# riffle-CTL-0_2-throughhole.net
KiCad netlist of a schematic drawn in EAGLE
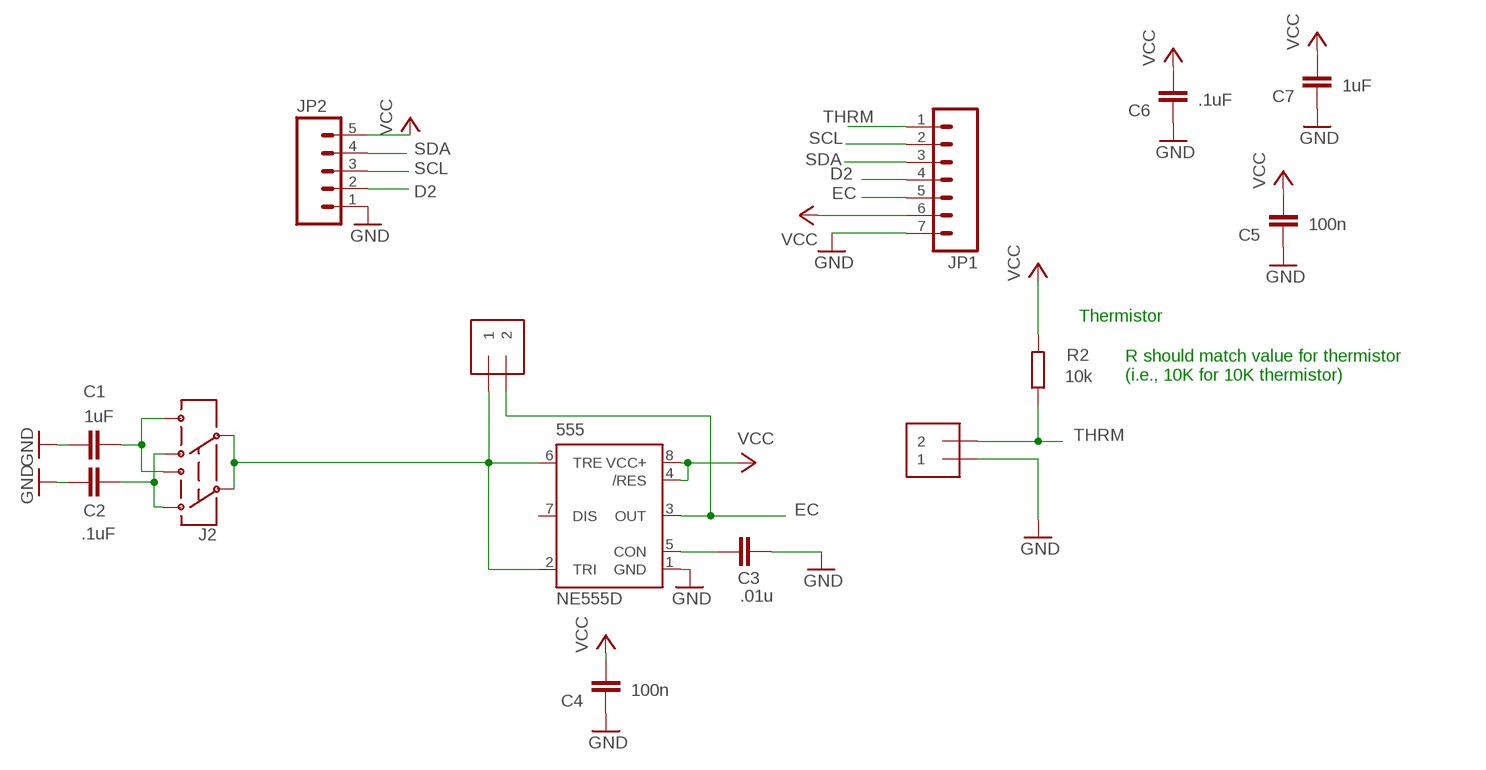
[diagram p0: schematic, sheet 1]

(export (version "E")
  (design (tool "Eeschema 10.0.6"))
  (components
    (comp (ref "555")
      (value "NE555D")
      (footprint "eagle-import:SO08@1")
      (libsource (lib "eagle-import") (part "NE555D"))
    )
    (comp (ref "C1")
      (value "1uF")
      (footprint "eagle-import:C0805")
      (libsource (lib "eagle-import") (part "C-EUC0805"))
    )
    (comp (ref "C2")
      (value ".1uF")
      (footprint "eagle-import:C0805")
      (libsource (lib "eagle-import") (part "C-EUC0805"))
    )
    (comp (ref "C3")
      (value ".01u")
      (footprint "eagle-import:C0805")
      (libsource (lib "eagle-import") (part "C-EUC0805"))
    )
    (comp (ref "C4")
      (value "100n")
      (footprint "eagle-import:C0805")
      (libsource (lib "eagle-import") (part "C-EUC0805"))
    )
    (comp (ref "C5")
      (value "100n")
      (footprint "eagle-import:C0805")
      (libsource (lib "eagle-import") (part "C-EUC0805"))
    )
    (comp (ref "C6")
      (value ".1uF")
      (footprint "eagle-import:C0805")
      (libsource (lib "eagle-import") (part "C-EUC0805"))
    )
    (comp (ref "C7")
      (value "1uF")
      (footprint "eagle-import:C0805")
      (libsource (lib "eagle-import") (part "C-EUC0805"))
    )
    (comp (ref "EC")
      (value "1X2-3.5MM")
      (footprint "eagle-import:1X2-3.5MM")
      (libsource (lib "eagle-import") (part "1X2-3.5MM"))
    )
    (comp (ref "J2")
      (value "AYZ0202")
      (footprint "eagle-import:AYZ0202")
      (libsource (lib "eagle-import") (part "AYZ0202"))
    )
    (comp (ref "JP1")
      (value "M07")
      (footprint "eagle-import:1X07")
      (libsource (lib "eagle-import") (part "M07"))
    )
    (comp (ref "JP2")
      (value "M05PTH")
      (footprint "eagle-import:1X05")
      (libsource (lib "eagle-import") (part "M05PTH"))
    )
    (comp (ref "R2")
      (value "10k")
      (footprint "eagle-import:R0805")
      (libsource (lib "eagle-import") (part "R-EU_R0805"))
    )
    (comp (ref "THRM")
      (value "1X2-3.5MM")
      (footprint "eagle-import:1X2-3.5MM")
      (libsource (lib "eagle-import") (part "1X2-3.5MM"))
    )
  )
  (nets
    (net (code "1") (name "/D2") (class "Default")
      (node (ref "JP1") (pin "4") (pinfunction "4_4") (pintype "passive"))
      (node (ref "JP2") (pin "2") (pinfunction "2_2") (pintype "passive"))
    )
    (net (code "2") (name "/EC") (class "Default")
      (node (ref "555") (pin "3") (pinfunction "OUT_3") (pintype "output"))
      (node (ref "EC") (pin "2") (pinfunction "2_2") (pintype "passive"))
      (node (ref "JP1") (pin "5") (pinfunction "5_5") (pintype "passive"))
    )
    (net (code "3") (name "/SCL") (class "Default")
      (node (ref "JP1") (pin "2") (pinfunction "2_2") (pintype "passive"))
      (node (ref "JP2") (pin "3") (pinfunction "3_3") (pintype "passive"))
    )
    (net (code "4") (name "/SDA") (class "Default")
      (node (ref "JP1") (pin "3") (pinfunction "3_3") (pintype "passive"))
      (node (ref "JP2") (pin "4") (pinfunction "4_4") (pintype "passive"))
    )
    (net (code "5") (name "/THRM") (class "Default")
      (node (ref "JP1") (pin "1") (pinfunction "1_1") (pintype "passive"))
      (node (ref "R2") (pin "1") (pinfunction "1_1") (pintype "passive"))
      (node (ref "THRM") (pin "2") (pinfunction "2_2") (pintype "passive"))
    )
    (net (code "6") (name "GND") (class "Default")
      (node (ref "555") (pin "1") (pinfunction "GND_1") (pintype "power_in"))
      (node (ref "C1") (pin "2") (pinfunction "2_2") (pintype "passive"))
      (node (ref "C2") (pin "2") (pinfunction "2_2") (pintype "passive"))
      (node (ref "C3") (pin "1") (pinfunction "1_1") (pintype "passive"))
      (node (ref "C4") (pin "1") (pinfunction "1_1") (pintype "passive"))
      (node (ref "C5") (pin "1") (pinfunction "1_1") (pintype "passive"))
      (node (ref "C6") (pin "1") (pinfunction "1_1") (pintype "passive"))
      (node (ref "C7") (pin "1") (pinfunction "1_1") (pintype "passive"))
      (node (ref "JP1") (pin "7") (pinfunction "7_7") (pintype "passive"))
      (node (ref "JP2") (pin "1") (pinfunction "1_1") (pintype "passive"))
      (node (ref "THRM") (pin "1") (pinfunction "1_1") (pintype "passive"))
    )
    (net (code "7") (name "Net-(555-CON)") (class "Default")
      (node (ref "555") (pin "5") (pinfunction "CON_5") (pintype "input"))
      (node (ref "C3") (pin "2") (pinfunction "2_2") (pintype "passive"))
    )
    (net (code "8") (name "Net-(555-TRE)") (class "Default")
      (node (ref "555") (pin "2") (pinfunction "TRI_2") (pintype "input"))
      (node (ref "555") (pin "6") (pinfunction "TRE_6") (pintype "input"))
      (node (ref "EC") (pin "1") (pinfunction "1_1") (pintype "passive"))
      (node (ref "J2") (pin "2") (pinfunction "2_2") (pintype "bidirectional"))
      (node (ref "J2") (pin "5") (pinfunction "5_5") (pintype "bidirectional"))
    )
    (net (code "9") (name "Net-(J2-1)") (class "Default")
      (node (ref "C2") (pin "1") (pinfunction "1_1") (pintype "passive"))
      (node (ref "J2") (pin "3") (pinfunction "1_3") (pintype "bidirectional"))
      (node (ref "J2") (pin "6") (pinfunction "4_6") (pintype "bidirectional"))
    )
    (net (code "10") (name "Net-(J2-3)") (class "Default")
      (node (ref "C1") (pin "1") (pinfunction "1_1") (pintype "passive"))
      (node (ref "J2") (pin "1") (pinfunction "3_1") (pintype "bidirectional"))
      (node (ref "J2") (pin "4") (pinfunction "6_4") (pintype "bidirectional"))
    )
    (net (code "11") (name "VCC") (class "Default")
      (node (ref "555") (pin "4") (pinfunction "/RES_4") (pintype "input"))
      (node (ref "555") (pin "8") (pinfunction "VCC+_8") (pintype "power_in"))
      (node (ref "C4") (pin "2") (pinfunction "2_2") (pintype "passive"))
      (node (ref "C5") (pin "2") (pinfunction "2_2") (pintype "passive"))
      (node (ref "C6") (pin "2") (pinfunction "2_2") (pintype "passive"))
      (node (ref "C7") (pin "2") (pinfunction "2_2") (pintype "passive"))
      (node (ref "JP1") (pin "6") (pinfunction "6_6") (pintype "passive"))
      (node (ref "JP2") (pin "5") (pinfunction "5_5") (pintype "passive"))
      (node (ref "R2") (pin "2") (pinfunction "2_2") (pintype "passive"))
    )
    (net (code "12") (name "unconnected-(555-DIS-Pad7)") (class "Default")
      (node (ref "555") (pin "7") (pinfunction "DIS_7") (pintype "input"))
    )
  )
)
